# M8-420mA.net
KiCad netlist of a schematic drawn in EAGLE
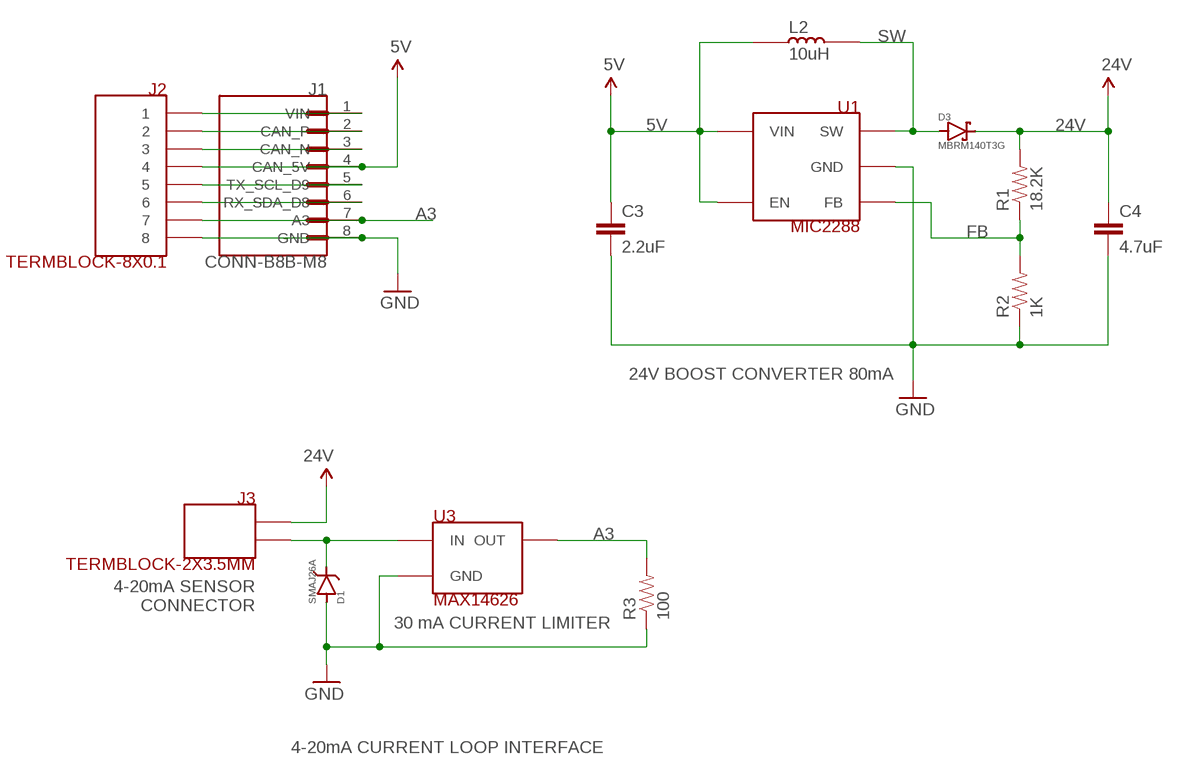
[diagram p0: schematic, sheet 1]

(export (version "E")
  (design (tool "Eeschema 10.0.6"))
  (components
    (comp (ref "C3")
      (value "2.2uF")
      (footprint "eagle-import:0603-CAP")
      (libsource (lib "eagle-import") (part "CAP-2.2UF-0603"))
    )
    (comp (ref "C4")
      (value "4.7uF")
      (footprint "eagle-import:0805")
      (libsource (lib "eagle-import") (part "CAP-4.7UF-25V-0805"))
    )
    (comp (ref "D1")
      (value "SMAJ26A")
      (footprint "eagle-import:DO-214AC-LITTELFUSE")
      (libsource (lib "eagle-import") (part "DIODE-TVS-SMAJ26A"))
    )
    (comp (ref "D3")
      (value "MBRM140T3G")
      (footprint "eagle-import:MBRM140T3G")
      (libsource (lib "eagle-import") (part "MBRM140T3G"))
    )
    (comp (ref "J1")
      (value "CONN-B8B-M8")
      (footprint "eagle-import:JST_B8B-PH-SM4-TB(LF)(SN)")
      (libsource (lib "eagle-import") (part "CONN-B8B-M8"))
    )
    (comp (ref "J2")
      (value "TERMBLOCK-8X0.1")
      (footprint "eagle-import:TERMBLOCK-8X0.1")
      (libsource (lib "eagle-import") (part "TERMBLOCK-8X0.1"))
    )
    (comp (ref "J3")
      (value "TERMBLOCK-2X3.5MM")
      (footprint "eagle-import:TERMBLOCK-2X3.5MM")
      (libsource (lib "eagle-import") (part "TERMBLOCK-2X3.5MM"))
    )
    (comp (ref "L2")
      (value "10uH")
      (footprint "eagle-import:BOURNS-INDUCTOR-3X3")
      (libsource (lib "eagle-import") (part "INDUCTOR-10UH"))
    )
    (comp (ref "R1")
      (value "18.2K")
      (footprint "eagle-import:0603-RES")
      (libsource (lib "eagle-import") (part "RES-18.2K-06030603"))
    )
    (comp (ref "R2")
      (value "1K")
      (footprint "eagle-import:0603-RES")
      (libsource (lib "eagle-import") (part "RES-1K-0603"))
    )
    (comp (ref "R3")
      (value "100")
      (footprint "eagle-import:0603-RES")
      (libsource (lib "eagle-import") (part "RES-100-0603.DEV"))
    )
    (comp (ref "U1")
      (value "MIC2288")
      (footprint "eagle-import:TSOT23-5-MICROCHIP")
      (libsource (lib "eagle-import") (part "MIC2288"))
    )
    (comp (ref "U3")
      (value "MAX14626")
      (footprint "eagle-import:6-TDFN-MAXIM")
      (libsource (lib "eagle-import") (part "MAX14626"))
    )
  )
  (nets
    (net (code "1") (name "/A3") (class "Default")
      (node (ref "J1") (pin "7") (pinfunction "A3_7") (pintype "passive"))
      (node (ref "J2") (pin "P$7") (pinfunction "7_P$7") (pintype "passive"))
      (node (ref "R3") (pin "2") (pinfunction "2_2") (pintype "passive"))
      (node (ref "U3") (pin "6") (pinfunction "OUT_6") (pintype "bidirectional"))
    )
    (net (code "2") (name "/FB") (class "Default")
      (node (ref "R1") (pin "1") (pinfunction "1_1") (pintype "passive"))
      (node (ref "R2") (pin "2") (pinfunction "2_2") (pintype "passive"))
      (node (ref "U1") (pin "3") (pinfunction "FB_3") (pintype "input"))
    )
    (net (code "3") (name "/SW") (class "Default")
      (node (ref "D3") (pin "2") (pinfunction "ANODE_2") (pintype "bidirectional"))
      (node (ref "L2") (pin "2") (pinfunction "P$2_2") (pintype "passive"))
      (node (ref "U1") (pin "1") (pinfunction "SW_1") (pintype "output"))
    )
    (net (code "4") (name "5V") (class "Default")
      (node (ref "C3") (pin "1") (pinfunction "1_1") (pintype "passive"))
      (node (ref "J1") (pin "4") (pinfunction "CAN_5V_4") (pintype "passive"))
      (node (ref "J2") (pin "P$4") (pinfunction "4_P$4") (pintype "passive"))
      (node (ref "L2") (pin "1") (pinfunction "P$1_1") (pintype "passive"))
      (node (ref "U1") (pin "4") (pinfunction "EN_4") (pintype "input"))
      (node (ref "U1") (pin "5") (pinfunction "VIN_5") (pintype "power_in"))
    )
    (net (code "5") (name "24V") (class "Default")
      (node (ref "C4") (pin "1") (pinfunction "1_1") (pintype "passive"))
      (node (ref "D3") (pin "1") (pinfunction "CATHODE_1") (pintype "bidirectional"))
      (node (ref "J3") (pin "1") (pinfunction "1_1") (pintype "passive"))
      (node (ref "R1") (pin "2") (pinfunction "2_2") (pintype "passive"))
    )
    (net (code "6") (name "GND") (class "Default")
      (node (ref "C3") (pin "2") (pinfunction "2_2") (pintype "passive"))
      (node (ref "C4") (pin "2") (pinfunction "2_2") (pintype "passive"))
      (node (ref "D1") (pin "A") (pinfunction "ANODE_A") (pintype "bidirectional"))
      (node (ref "J1") (pin "8") (pinfunction "GND_8") (pintype "passive"))
      (node (ref "J2") (pin "P$8") (pinfunction "8_P$8") (pintype "passive"))
      (node (ref "R2") (pin "1") (pinfunction "1_1") (pintype "passive"))
      (node (ref "R3") (pin "1") (pinfunction "1_1") (pintype "passive"))
      (node (ref "U1") (pin "2") (pinfunction "GND_2") (pintype "passive"))
      (node (ref "U3") (pin "2") (pinfunction "GND_2") (pintype "passive"))
      (node (ref "U3") (pin "3") (pinfunction "GND_3") (pintype "passive"))
      (node (ref "U3") (pin "4") (pinfunction "GND_4") (pintype "passive"))
      (node (ref "U3") (pin "5") (pinfunction "GND_5") (pintype "passive"))
      (node (ref "U3") (pin "EP") (pinfunction "GND_EP") (pintype "passive"))
    )
    (net (code "7") (name "Net-(D1-CATHODE)") (class "Default")
      (node (ref "D1") (pin "C") (pinfunction "CATHODE_C") (pintype "bidirectional"))
      (node (ref "J3") (pin "2") (pinfunction "2_2") (pintype "passive"))
      (node (ref "U3") (pin "1") (pinfunction "IN_1") (pintype "passive"))
    )
    (net (code "8") (name "Net-(J1-CAN_N)") (class "Default")
      (node (ref "J1") (pin "3") (pinfunction "CAN_N_3") (pintype "passive"))
      (node (ref "J2") (pin "P$3") (pinfunction "3_P$3") (pintype "passive"))
    )
    (net (code "9") (name "Net-(J1-CAN_P)") (class "Default")
      (node (ref "J1") (pin "2") (pinfunction "CAN_P_2") (pintype "passive"))
      (node (ref "J2") (pin "P$2") (pinfunction "2_P$2") (pintype "passive"))
    )
    (net (code "10") (name "Net-(J1-RX_SDA_D8)") (class "Default")
      (node (ref "J1") (pin "6") (pinfunction "RX_SDA_D8_6") (pintype "passive"))
      (node (ref "J2") (pin "P$6") (pinfunction "6_P$6") (pintype "passive"))
    )
    (net (code "11") (name "Net-(J1-TX_SCL_D9)") (class "Default")
      (node (ref "J1") (pin "5") (pinfunction "TX_SCL_D9_5") (pintype "passive"))
      (node (ref "J2") (pin "P$5") (pinfunction "5_P$5") (pintype "passive"))
    )
    (net (code "12") (name "Net-(J1-VIN)") (class "Default")
      (node (ref "J1") (pin "1") (pinfunction "VIN_1") (pintype "passive"))
      (node (ref "J2") (pin "P$1") (pinfunction "1_P$1") (pintype "passive"))
    )
  )
)
